# ProPrj_AGB_2024-12-26.net
KiCad netlist of a schematic drawn in EasyEDA Pro
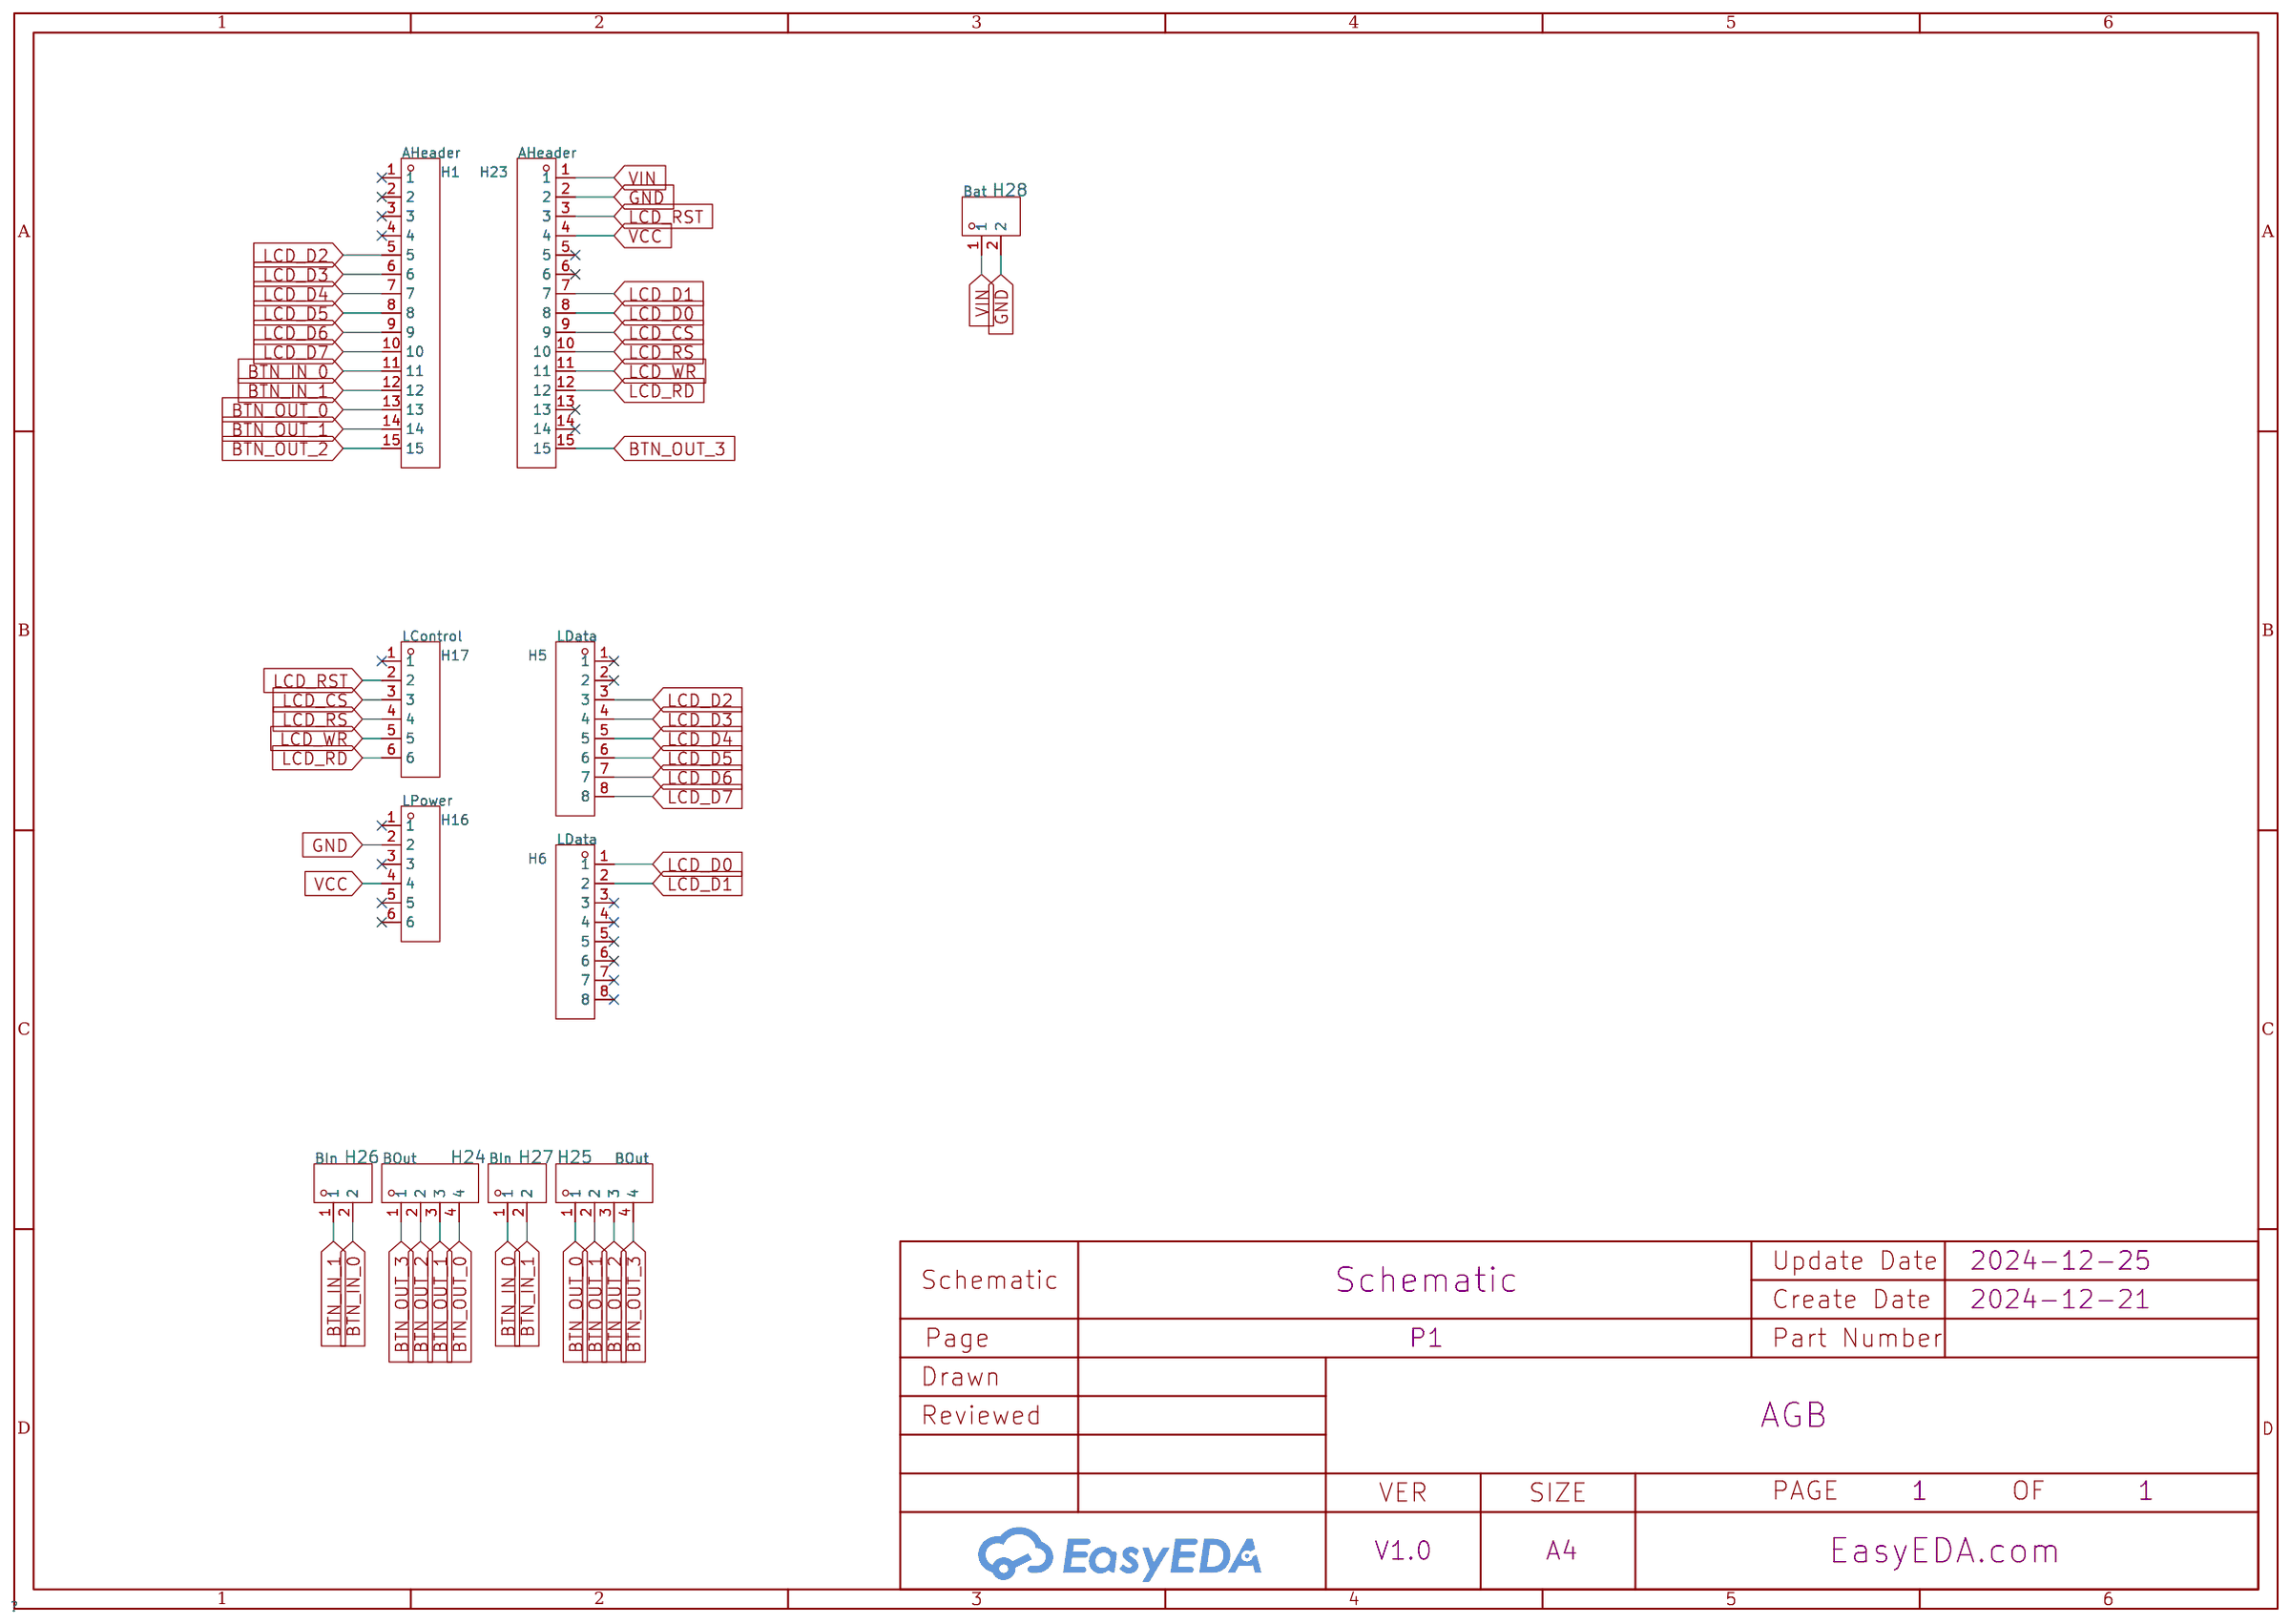
[diagram p0: schematic sheet]

(export (version "E")
  (design (tool "Eeschema 10.0.6"))
  (components
    (comp (ref "H1")
      (value "AHeader")
      (footprint "easyedapro:HDR-TH_15P-P2.54-V-F")
      (description "Holes Structure:1x15P Pitch:2.54mm Number of Rows:Plugin Contact Plating:Gold")
      (fields (field (name "Manufacturer Part") "PM2.54-1*15") (field (name "Manufacturer") "ZHOURI(洲日)"))
      (libsource (lib "easyedapro") (part "PM2.54-1*15"))
    )
    (comp (ref "H5")
      (value "LData")
      (footprint "easyedapro:HDR-TH_8P-P2.54-V-F")
      (fields (field (name "Manufacturer Part") "PM2.54-1*8") (field (name "Manufacturer") "ZHOURI(洲日)"))
      (libsource (lib "easyedapro") (part "PM2.54-1*8"))
    )
    (comp (ref "H6")
      (value "LData")
      (footprint "easyedapro:HDR-TH_8P-P2.54-V-F")
      (fields (field (name "Manufacturer Part") "PM2.54-1*8") (field (name "Manufacturer") "ZHOURI(洲日)"))
      (libsource (lib "easyedapro") (part "PM2.54-1*8"))
    )
    (comp (ref "H16")
      (value "LPower")
      (footprint "easyedapro:HDR-TH_6P-P2.54-V-F_4")
      (fields (field (name "Manufacturer Part") "PM2.54-1*6") (field (name "Manufacturer") "ZHOURI(洲日)"))
      (libsource (lib "easyedapro") (part "PM2.54-1*6"))
    )
    (comp (ref "H17")
      (value "LControl")
      (footprint "easyedapro:HDR-TH_6P-P2.54-V-F_4")
      (fields (field (name "Manufacturer Part") "PM2.54-1*6") (field (name "Manufacturer") "ZHOURI(洲日)"))
      (libsource (lib "easyedapro") (part "PM2.54-1*6"))
    )
    (comp (ref "H23")
      (value "AHeader")
      (footprint "easyedapro:HDR-TH_15P-P2.54-V-F")
      (description "Holes Structure:1x15P Pitch:2.54mm Number of Rows:Plugin Contact Plating:Gold")
      (fields (field (name "Manufacturer Part") "PM2.54-1*15") (field (name "Manufacturer") "ZHOURI(洲日)"))
      (libsource (lib "easyedapro") (part "PM2.54-1*15"))
    )
    (comp (ref "H24")
      (value "BOut")
      (footprint "easyedapro:HDR-TH_4P-P2.54-H-M-W10.4-N")
      (fields
        (field (name "Manufacturer Part") "KH-2.54PH90-1X4P-L13.8")
        (field (name "Manufacturer") "kinghelm(金航标)")
      )
      (libsource (lib "easyedapro") (part "KH-2.54PH90-1X4P-L13.8"))
    )
    (comp (ref "H25")
      (value "BOut")
      (footprint "easyedapro:HDR-TH_4P-P2.54-H-M-W10.4-N")
      (fields
        (field (name "Manufacturer Part") "KH-2.54PH90-1X4P-L13.8")
        (field (name "Manufacturer") "kinghelm(金航标)")
      )
      (libsource (lib "easyedapro") (part "KH-2.54PH90-1X4P-L13.8"))
    )
    (comp (ref "H26")
      (value "BIn")
      (footprint "easyedapro:HDR-TH_2P-P2.54-H-M_KH-2.54PH90-1X2P-L13.8")
      (fields
        (field (name "Manufacturer Part") "KH-2.54PH90-1X2P-L13.8")
        (field (name "Manufacturer") "kinghelm(金航标)")
      )
      (libsource (lib "easyedapro") (part "KH-2.54PH90-1X2P-L13.8"))
    )
    (comp (ref "H27")
      (value "BIn")
      (footprint "easyedapro:HDR-TH_2P-P2.54-H-M_KH-2.54PH90-1X2P-L13.8")
      (fields
        (field (name "Manufacturer Part") "KH-2.54PH90-1X2P-L13.8")
        (field (name "Manufacturer") "kinghelm(金航标)")
      )
      (libsource (lib "easyedapro") (part "KH-2.54PH90-1X2P-L13.8"))
    )
    (comp (ref "H28")
      (value "Bat")
      (footprint "easyedapro:HDR-TH_2P-P2.54-H-M_KH-2.54PH90-1X2P-L13.8")
      (fields
        (field (name "Manufacturer Part") "KH-2.54PH90-1X2P-L13.8")
        (field (name "Manufacturer") "kinghelm(金航标)")
      )
      (libsource (lib "easyedapro") (part "KH-2.54PH90-1X2P-L13.8"))
    )
  )
  (nets
    (net (code "1") (name "BTN_IN_0") (class "Default")
      (node (ref "H1") (pin "11") (pinfunction "11_11") (pintype "unspecified"))
      (node (ref "H26") (pin "2") (pinfunction "2_2") (pintype "input"))
      (node (ref "H27") (pin "1") (pinfunction "1_1") (pintype "input"))
    )
    (net (code "2") (name "BTN_IN_1") (class "Default")
      (node (ref "H1") (pin "12") (pinfunction "12_12") (pintype "unspecified"))
      (node (ref "H26") (pin "1") (pinfunction "1_1") (pintype "input"))
      (node (ref "H27") (pin "2") (pinfunction "2_2") (pintype "input"))
    )
    (net (code "3") (name "BTN_OUT_0") (class "Default")
      (node (ref "H1") (pin "13") (pinfunction "13_13") (pintype "unspecified"))
      (node (ref "H24") (pin "4") (pinfunction "4_4") (pintype "input"))
      (node (ref "H25") (pin "1") (pinfunction "1_1") (pintype "input"))
    )
    (net (code "4") (name "BTN_OUT_1") (class "Default")
      (node (ref "H1") (pin "14") (pinfunction "14_14") (pintype "unspecified"))
      (node (ref "H24") (pin "3") (pinfunction "3_3") (pintype "input"))
      (node (ref "H25") (pin "2") (pinfunction "2_2") (pintype "input"))
    )
    (net (code "5") (name "BTN_OUT_2") (class "Default")
      (node (ref "H1") (pin "15") (pinfunction "15_15") (pintype "unspecified"))
      (node (ref "H24") (pin "2") (pinfunction "2_2") (pintype "input"))
      (node (ref "H25") (pin "3") (pinfunction "3_3") (pintype "input"))
    )
    (net (code "6") (name "BTN_OUT_3") (class "Default")
      (node (ref "H23") (pin "15") (pinfunction "15_15") (pintype "unspecified"))
      (node (ref "H24") (pin "1") (pinfunction "1_1") (pintype "input"))
      (node (ref "H25") (pin "4") (pinfunction "4_4") (pintype "input"))
    )
    (net (code "7") (name "GND") (class "Default")
      (node (ref "H16") (pin "2") (pinfunction "2_2") (pintype "unspecified"))
      (node (ref "H23") (pin "2") (pinfunction "2_2") (pintype "unspecified"))
      (node (ref "H28") (pin "2") (pinfunction "2_2") (pintype "input"))
    )
    (net (code "8") (name "LCD_CS") (class "Default")
      (node (ref "H17") (pin "3") (pinfunction "3_3") (pintype "unspecified"))
      (node (ref "H23") (pin "9") (pinfunction "9_9") (pintype "unspecified"))
    )
    (net (code "9") (name "LCD_D0") (class "Default")
      (node (ref "H23") (pin "8") (pinfunction "8_8") (pintype "unspecified"))
      (node (ref "H6") (pin "1") (pinfunction "1_1") (pintype "unspecified"))
    )
    (net (code "10") (name "LCD_D1") (class "Default")
      (node (ref "H23") (pin "7") (pinfunction "7_7") (pintype "unspecified"))
      (node (ref "H6") (pin "2") (pinfunction "2_2") (pintype "unspecified"))
    )
    (net (code "11") (name "LCD_D2") (class "Default")
      (node (ref "H1") (pin "5") (pinfunction "5_5") (pintype "unspecified"))
      (node (ref "H5") (pin "3") (pinfunction "3_3") (pintype "unspecified"))
    )
    (net (code "12") (name "LCD_D3") (class "Default")
      (node (ref "H1") (pin "6") (pinfunction "6_6") (pintype "unspecified"))
      (node (ref "H5") (pin "4") (pinfunction "4_4") (pintype "unspecified"))
    )
    (net (code "13") (name "LCD_D4") (class "Default")
      (node (ref "H1") (pin "7") (pinfunction "7_7") (pintype "unspecified"))
      (node (ref "H5") (pin "5") (pinfunction "5_5") (pintype "unspecified"))
    )
    (net (code "14") (name "LCD_D5") (class "Default")
      (node (ref "H1") (pin "8") (pinfunction "8_8") (pintype "unspecified"))
      (node (ref "H5") (pin "6") (pinfunction "6_6") (pintype "unspecified"))
    )
    (net (code "15") (name "LCD_D6") (class "Default")
      (node (ref "H1") (pin "9") (pinfunction "9_9") (pintype "unspecified"))
      (node (ref "H5") (pin "7") (pinfunction "7_7") (pintype "unspecified"))
    )
    (net (code "16") (name "LCD_D7") (class "Default")
      (node (ref "H1") (pin "10") (pinfunction "10_10") (pintype "unspecified"))
      (node (ref "H5") (pin "8") (pinfunction "8_8") (pintype "unspecified"))
    )
    (net (code "17") (name "LCD_RD") (class "Default")
      (node (ref "H17") (pin "6") (pinfunction "6_6") (pintype "unspecified"))
      (node (ref "H23") (pin "12") (pinfunction "12_12") (pintype "unspecified"))
    )
    (net (code "18") (name "LCD_RS") (class "Default")
      (node (ref "H17") (pin "4") (pinfunction "4_4") (pintype "unspecified"))
      (node (ref "H23") (pin "10") (pinfunction "10_10") (pintype "unspecified"))
    )
    (net (code "19") (name "LCD_RST") (class "Default")
      (node (ref "H17") (pin "2") (pinfunction "2_2") (pintype "unspecified"))
      (node (ref "H23") (pin "3") (pinfunction "3_3") (pintype "unspecified"))
    )
    (net (code "20") (name "LCD_WR") (class "Default")
      (node (ref "H17") (pin "5") (pinfunction "5_5") (pintype "unspecified"))
      (node (ref "H23") (pin "11") (pinfunction "11_11") (pintype "unspecified"))
    )
    (net (code "21") (name "VCC") (class "Default")
      (node (ref "H16") (pin "4") (pinfunction "4_4") (pintype "unspecified"))
      (node (ref "H23") (pin "4") (pinfunction "4_4") (pintype "unspecified"))
    )
    (net (code "22") (name "VIN") (class "Default")
      (node (ref "H23") (pin "1") (pinfunction "1_1") (pintype "unspecified"))
      (node (ref "H28") (pin "1") (pinfunction "1_1") (pintype "input"))
    )
    (net (code "23") (name "unconnected-(H1-Pad1)") (class "Default")
      (node (ref "H1") (pin "1") (pinfunction "1_1") (pintype "unspecified+no_connect"))
    )
    (net (code "24") (name "unconnected-(H1-Pad2)") (class "Default")
      (node (ref "H1") (pin "2") (pinfunction "2_2") (pintype "unspecified+no_connect"))
    )
    (net (code "25") (name "unconnected-(H1-Pad3)") (class "Default")
      (node (ref "H1") (pin "3") (pinfunction "3_3") (pintype "unspecified+no_connect"))
    )
    (net (code "26") (name "unconnected-(H1-Pad4)") (class "Default")
      (node (ref "H1") (pin "4") (pinfunction "4_4") (pintype "unspecified+no_connect"))
    )
    (net (code "27") (name "unconnected-(H5-Pad1)") (class "Default")
      (node (ref "H5") (pin "1") (pinfunction "1_1") (pintype "unspecified+no_connect"))
    )
    (net (code "28") (name "unconnected-(H5-Pad2)") (class "Default")
      (node (ref "H5") (pin "2") (pinfunction "2_2") (pintype "unspecified+no_connect"))
    )
    (net (code "29") (name "unconnected-(H6-Pad3)") (class "Default")
      (node (ref "H6") (pin "3") (pinfunction "3_3") (pintype "unspecified+no_connect"))
    )
    (net (code "30") (name "unconnected-(H6-Pad4)") (class "Default")
      (node (ref "H6") (pin "4") (pinfunction "4_4") (pintype "unspecified+no_connect"))
    )
    (net (code "31") (name "unconnected-(H6-Pad5)") (class "Default")
      (node (ref "H6") (pin "5") (pinfunction "5_5") (pintype "unspecified+no_connect"))
    )
    (net (code "32") (name "unconnected-(H6-Pad6)") (class "Default")
      (node (ref "H6") (pin "6") (pinfunction "6_6") (pintype "unspecified+no_connect"))
    )
    (net (code "33") (name "unconnected-(H6-Pad7)") (class "Default")
      (node (ref "H6") (pin "7") (pinfunction "7_7") (pintype "unspecified+no_connect"))
    )
    (net (code "34") (name "unconnected-(H6-Pad8)") (class "Default")
      (node (ref "H6") (pin "8") (pinfunction "8_8") (pintype "unspecified+no_connect"))
    )
    (net (code "35") (name "unconnected-(H16-Pad1)") (class "Default")
      (node (ref "H16") (pin "1") (pinfunction "1_1") (pintype "unspecified+no_connect"))
    )
    (net (code "36") (name "unconnected-(H16-Pad3)") (class "Default")
      (node (ref "H16") (pin "3") (pinfunction "3_3") (pintype "unspecified+no_connect"))
    )
    (net (code "37") (name "unconnected-(H16-Pad5)") (class "Default")
      (node (ref "H16") (pin "5") (pinfunction "5_5") (pintype "unspecified+no_connect"))
    )
    (net (code "38") (name "unconnected-(H16-Pad6)") (class "Default")
      (node (ref "H16") (pin "6") (pinfunction "6_6") (pintype "unspecified+no_connect"))
    )
    (net (code "39") (name "unconnected-(H17-Pad1)") (class "Default")
      (node (ref "H17") (pin "1") (pinfunction "1_1") (pintype "unspecified+no_connect"))
    )
    (net (code "40") (name "unconnected-(H23-Pad5)") (class "Default")
      (node (ref "H23") (pin "5") (pinfunction "5_5") (pintype "unspecified+no_connect"))
    )
    (net (code "41") (name "unconnected-(H23-Pad6)") (class "Default")
      (node (ref "H23") (pin "6") (pinfunction "6_6") (pintype "unspecified+no_connect"))
    )
    (net (code "42") (name "unconnected-(H23-Pad13)") (class "Default")
      (node (ref "H23") (pin "13") (pinfunction "13_13") (pintype "unspecified+no_connect"))
    )
    (net (code "43") (name "unconnected-(H23-Pad14)") (class "Default")
      (node (ref "H23") (pin "14") (pinfunction "14_14") (pintype "unspecified+no_connect"))
    )
  )
)
